# SoM.net
KiCad netlist of a schematic drawn in Altium Designer
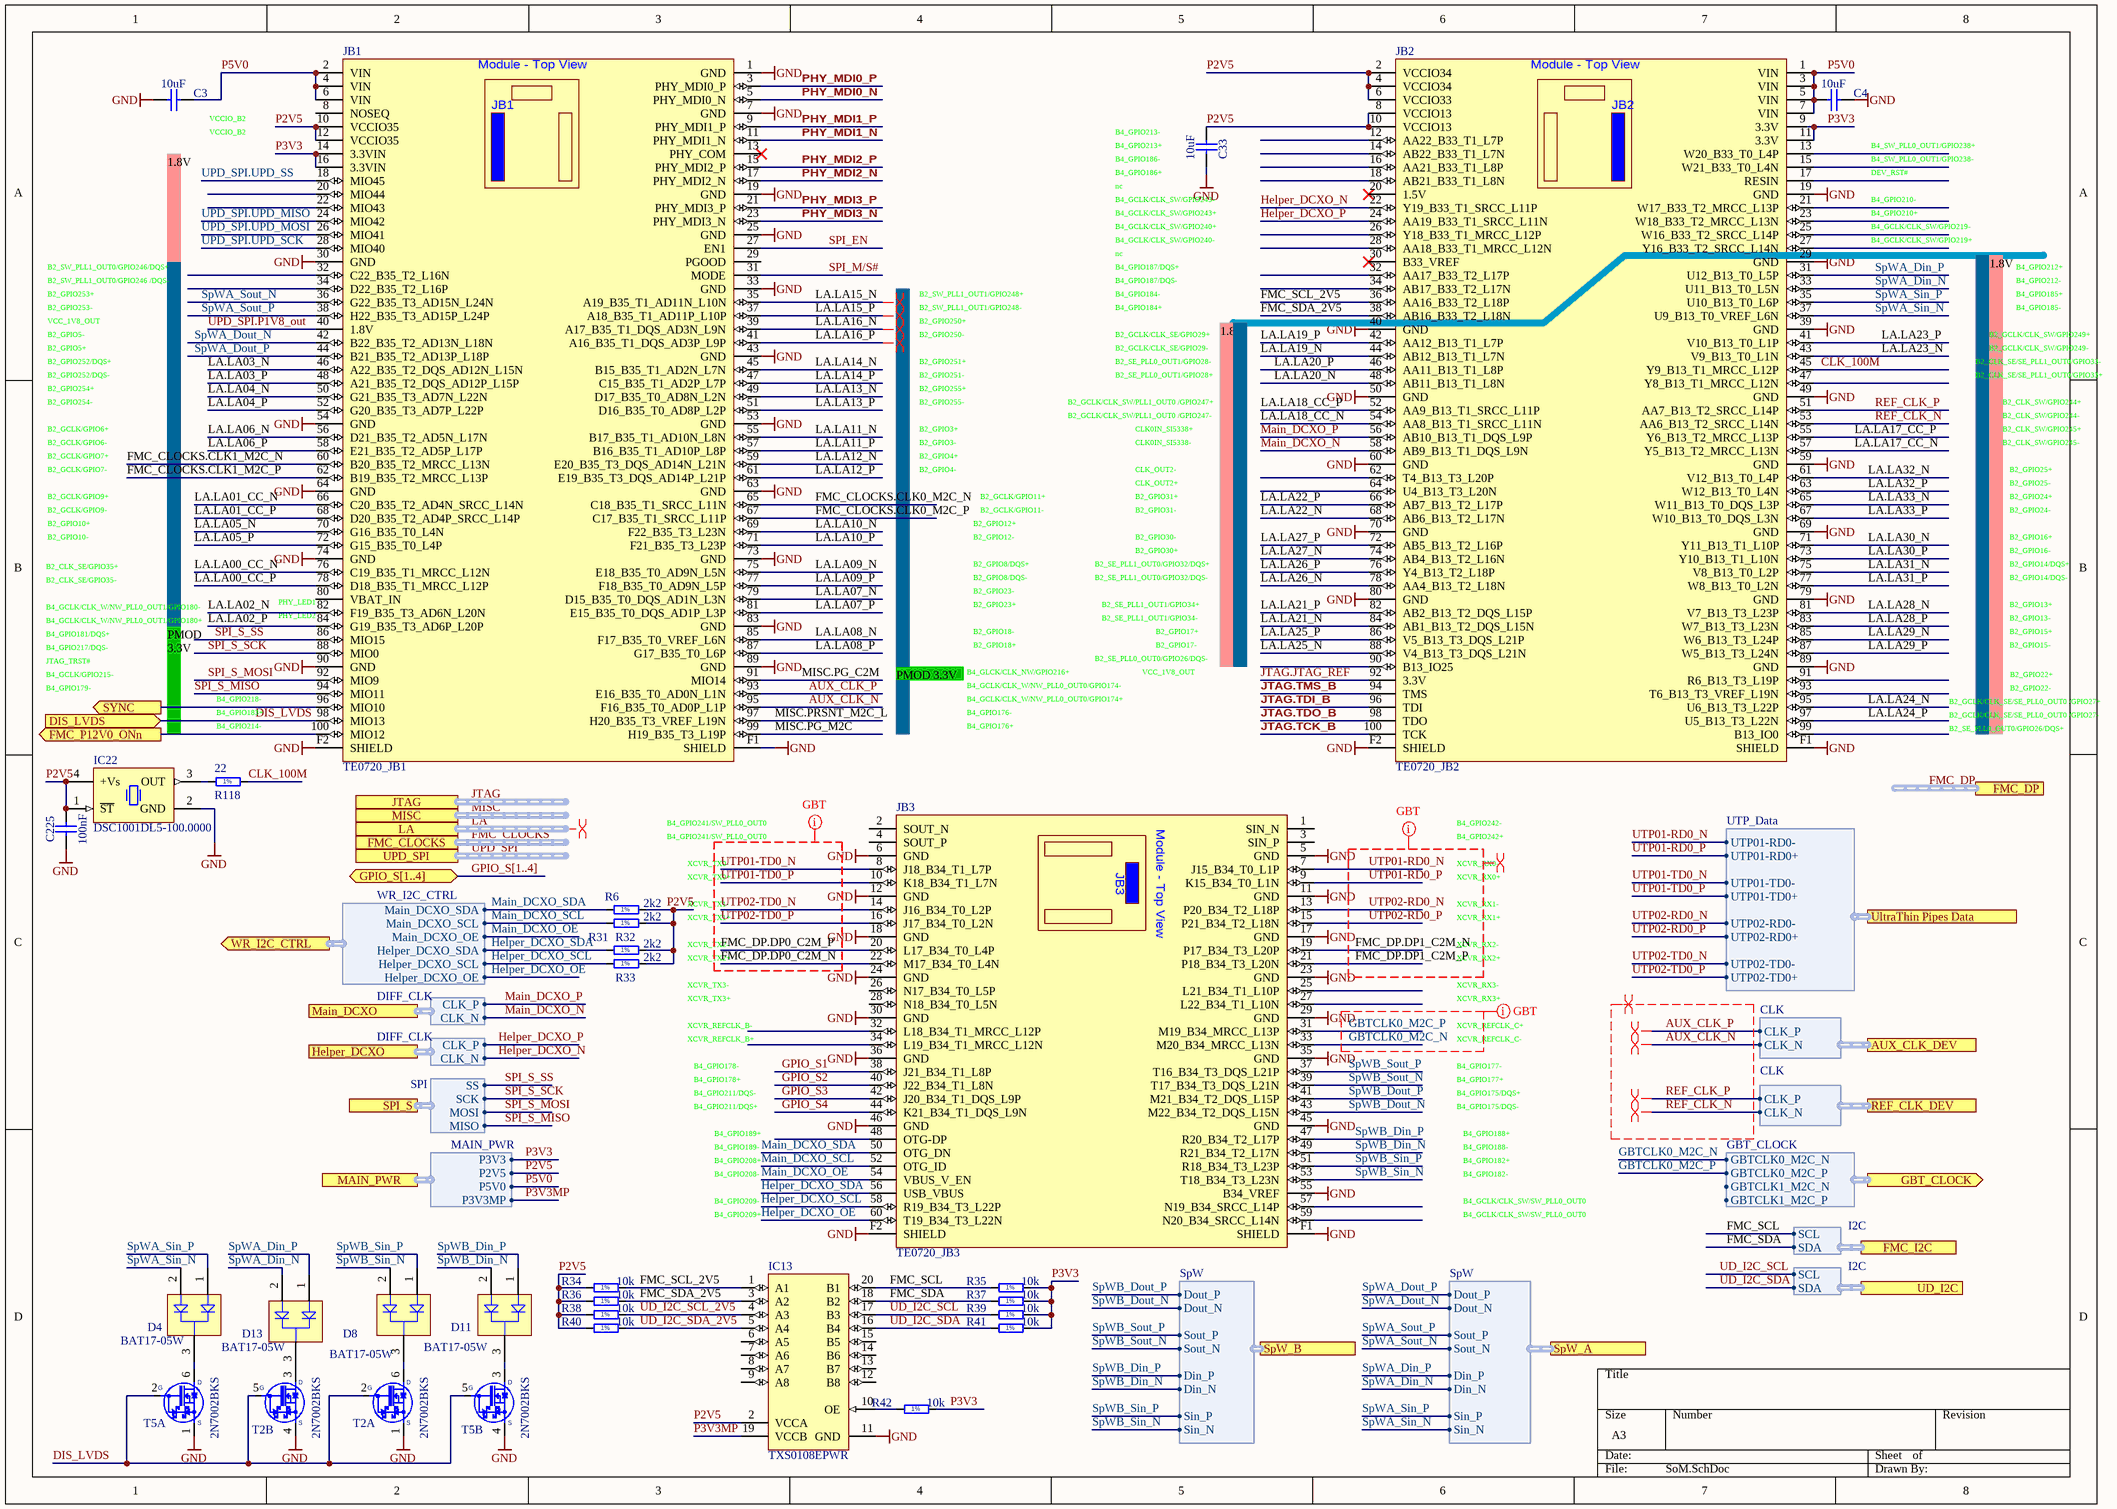
[diagram p0: SoM.SchDoc]

(export (version "E")
  (design (tool "Eeschema 10.0.6"))
  (components
    (comp (ref "C3")
      (value "10uF")
      (footprint "CAPC2012X95N")
      (description "Non-polarised capacitor")
      (fields (field (name "PART NUMBER") "CC0805_10UF_25V_10%_X5R") (field (name "VOLTAGE") "25V"))
      (libsource (lib "Capacitors") (part "Capacitor - non polarized"))
    )
    (comp (ref "C4")
      (value "10uF")
      (footprint "CAPC2012X95N")
      (description "Non-polarised capacitor")
      (fields (field (name "PART NUMBER") "CC0805_10UF_25V_10%_X5R") (field (name "VOLTAGE") "25V"))
      (libsource (lib "Capacitors") (part "Capacitor - non polarized"))
    )
    (comp (ref "C33")
      (value "10uF")
      (footprint "CAPC2012X95N")
      (description "Non-polarised capacitor")
      (fields (field (name "PART NUMBER") "CC0805_10UF_25V_10%_X5R") (field (name "VOLTAGE") "25V"))
      (libsource (lib "Capacitors") (part "Capacitor - non polarized"))
    )
    (comp (ref "C225")
      (value "100nF")
      (footprint "CAPC0603X33N")
      (description "Non-polarised capacitor")
      (fields
        (field (name "PART NUMBER") "CC0201_100NF_6.3V_10%_X5R")
        (field (name "MANUFACTURER") "GENERIC")
      )
      (libsource (lib "Capacitors") (part "Capacitor - non polarized"))
    )
    (comp (ref "D4")
      (value "BAT17-05W")
      (footprint "INF-SOT323_N")
      (description "Dual Silicon Schottky Diode, 130 mA IF Max, SOT323, Green")
      (fields (field (name "MANUFACTURER") "Infineon"))
      (libsource (lib "Altium Content Vault") (part "INF-D_A1A2K3-3"))
    )
    (comp (ref "D8")
      (value "BAT17-05W")
      (footprint "INF-SOT323_N")
      (description "Dual Silicon Schottky Diode, 130 mA IF Max, SOT323, Green")
      (fields (field (name "MANUFACTURER") "Infineon"))
      (libsource (lib "Altium Content Vault") (part "INF-D_A1A2K3-3"))
    )
    (comp (ref "D11")
      (value "BAT17-05W")
      (footprint "INF-SOT323_N")
      (description "Dual Silicon Schottky Diode, 130 mA IF Max, SOT323, Green")
      (fields (field (name "MANUFACTURER") "Infineon"))
      (libsource (lib "Altium Content Vault") (part "INF-D_A1A2K3-3"))
    )
    (comp (ref "D13")
      (value "BAT17-05W")
      (footprint "INF-SOT323_N")
      (description "Dual Silicon Schottky Diode, 130 mA IF Max, SOT323, Green")
      (fields (field (name "MANUFACTURER") "Infineon"))
      (libsource (lib "Altium Content Vault") (part "INF-D_A1A2K3-3"))
    )
    (comp (ref "IC13")
      (value "TXS0108EPWR")
      (footprint "PW0020A_M")
      (fields (field (name "MANUFACTURER") "Texas Instruments"))
      (libsource (lib "Altium Content Vault") (part "TI-TXS0108EPWR-SOP-20"))
    )
    (comp (ref "IC22")
      (value "DSC1001DL5-100.0000")
      (footprint "OSC_MICREL_2520")
      (description "MEMS 100MHz oscillator")
      (fields (field (name "MANUFACTURER") "Micrel"))
      (libsource (lib "LIBRARY_SCH") (part "OSC_DSC1001DL5-100.0000"))
    )
    (comp (ref "JB1")
      (value "TE0720_JB1")
      (footprint "LSHM-150-XXX-X-DV-A-X")
      (description "TE0720-JB1")
      (libsource (lib "TE") (part "TE0720_JB1"))
    )
    (comp (ref "JB2")
      (value "TE0720_JB2")
      (footprint "LSHM-150-XXX-X-DV-A-X")
      (description "TE0720-JB2")
      (libsource (lib "TE") (part "TE0720_JB2"))
    )
    (comp (ref "JB3")
      (value "TE0720_JB3")
      (footprint "LSHM-130-04.0-x-DV-A-S-K-TR")
      (description "TE0720-JB3")
      (libsource (lib "TE") (part "TE0720_JB3"))
    )
    (comp (ref "R6")
      (value "2k2")
      (footprint "RESC1005X40N")
      (description "Resistor - 1%")
      (fields (field (name "PART NUMBER") "R0402_2K2_1%_0.0625W_100PPM") (field (name "POWER") "0.0625W"))
      (libsource (lib "Resistors") (part "Resistor - 1%"))
    )
    (comp (ref "R31")
      (value "2k2")
      (footprint "RESC1005X40N")
      (description "Resistor - 1%")
      (fields (field (name "PART NUMBER") "R0402_2K2_1%_0.0625W_100PPM") (field (name "POWER") "0.0625W"))
      (libsource (lib "Resistors") (part "Resistor - 1%"))
    )
    (comp (ref "R32")
      (value "2k2")
      (footprint "RESC1005X40N")
      (description "Resistor - 1%")
      (fields (field (name "PART NUMBER") "R0402_2K2_1%_0.0625W_100PPM") (field (name "POWER") "0.0625W"))
      (libsource (lib "Resistors") (part "Resistor - 1%"))
    )
    (comp (ref "R33")
      (value "2k2")
      (footprint "RESC1005X40N")
      (description "Resistor - 1%")
      (fields (field (name "PART NUMBER") "R0402_2K2_1%_0.0625W_100PPM") (field (name "POWER") "0.0625W"))
      (libsource (lib "Resistors") (part "Resistor - 1%"))
    )
    (comp (ref "R34")
      (value "10k")
      (footprint "RESC1005X40N")
      (description "Resistor - 1%")
      (fields (field (name "PART NUMBER") "R0402_10K_1%_0.0625W_100PPM") (field (name "POWER") "0.0625W"))
      (libsource (lib "Resistors") (part "Resistor - 1%"))
    )
    (comp (ref "R35")
      (value "10k")
      (footprint "RESC1005X40N")
      (description "Resistor - 1%")
      (fields (field (name "PART NUMBER") "R0402_10K_1%_0.0625W_100PPM") (field (name "POWER") "0.0625W"))
      (libsource (lib "Resistors") (part "Resistor - 1%"))
    )
    (comp (ref "R36")
      (value "10k")
      (footprint "RESC1005X40N")
      (description "Resistor - 1%")
      (fields (field (name "PART NUMBER") "R0402_10K_1%_0.0625W_100PPM") (field (name "POWER") "0.0625W"))
      (libsource (lib "Resistors") (part "Resistor - 1%"))
    )
    (comp (ref "R37")
      (value "10k")
      (footprint "RESC1005X40N")
      (description "Resistor - 1%")
      (fields (field (name "PART NUMBER") "R0402_10K_1%_0.0625W_100PPM") (field (name "POWER") "0.0625W"))
      (libsource (lib "Resistors") (part "Resistor - 1%"))
    )
    (comp (ref "R38")
      (value "10k")
      (footprint "RESC1005X40N")
      (description "Resistor - 1%")
      (fields (field (name "PART NUMBER") "R0402_10K_1%_0.0625W_100PPM") (field (name "POWER") "0.0625W"))
      (libsource (lib "Resistors") (part "Resistor - 1%"))
    )
    (comp (ref "R39")
      (value "10k")
      (footprint "RESC1005X40N")
      (description "Resistor - 1%")
      (fields (field (name "PART NUMBER") "R0402_10K_1%_0.0625W_100PPM") (field (name "POWER") "0.0625W"))
      (libsource (lib "Resistors") (part "Resistor - 1%"))
    )
    (comp (ref "R40")
      (value "10k")
      (footprint "RESC1005X40N")
      (description "Resistor - 1%")
      (fields (field (name "PART NUMBER") "R0402_10K_1%_0.0625W_100PPM") (field (name "POWER") "0.0625W"))
      (libsource (lib "Resistors") (part "Resistor - 1%"))
    )
    (comp (ref "R41")
      (value "10k")
      (footprint "RESC1005X40N")
      (description "Resistor - 1%")
      (fields (field (name "PART NUMBER") "R0402_10K_1%_0.0625W_100PPM") (field (name "POWER") "0.0625W"))
      (libsource (lib "Resistors") (part "Resistor - 1%"))
    )
    (comp (ref "R42")
      (value "10k")
      (footprint "RESC1005X40N")
      (description "Resistor - 1%")
      (fields (field (name "PART NUMBER") "R0402_10K_1%_0.0625W_100PPM") (field (name "POWER") "0.0625W"))
      (libsource (lib "Resistors") (part "Resistor - 1%"))
    )
    (comp (ref "R118")
      (value "22")
      (footprint "RESC1005X40N")
      (description "Resistor - 1%")
      (fields (field (name "PART NUMBER") "R0402_22R_1%_0.0625W_100PPM") (field (name "POWER") "0.0625W"))
      (libsource (lib "Resistors") (part "Resistor - 1%"))
    )
    (comp (ref "T2")
      (value "2N7002BKS")
      (footprint "SOT65P210X110-6N")
      (description "60V, 300mA Dual N-Channel Trench MOSFET")
      (fields
        (field (name "MANUFACTURER") "NXP SEMICONDUCTORS")
        (field (name "MANUFACTURER PART NUMBER") "2N7002BKS6")
      )
      (libsource (lib "ICs And Semiconductors") (part "2N7002BKS"))
    )
    (comp (ref "T5")
      (value "2N7002BKS")
      (footprint "SOT65P210X110-6N")
      (description "60V, 300mA Dual N-Channel Trench MOSFET")
      (fields
        (field (name "MANUFACTURER") "NXP SEMICONDUCTORS")
        (field (name "MANUFACTURER PART NUMBER") "2N7002BKS6")
      )
      (libsource (lib "ICs And Semiconductors") (part "2N7002BKS"))
    )
  )
  (nets
    (net (code "16") (name "/AUX_CLK_N") (class "Default")
      (node (ref "JB1") (pin "95") (pinfunction "F16_B35_T0_AD0P_L1P_95") (pintype "bidirectional"))
    )
    (net (code "17") (name "/AUX_CLK_P") (class "Default")
      (node (ref "JB1") (pin "93") (pinfunction "E16_B35_T0_AD0N_L1N_93") (pintype "bidirectional"))
    )
    (net (code "40") (name "/CLK_100M") (class "Default")
      (node (ref "JB2") (pin "45") (pinfunction "Y9_B13_T1_MRCC_L12P_45") (pintype "bidirectional"))
      (node (ref "R118") (pin "2") (pinfunction "2_2") (pintype "passive"))
    )
    (net (code "41") (name "/DIS_LVDS") (class "Default")
      (node (ref "JB1") (pin "98") (pinfunction "MIO13_98") (pintype "bidirectional"))
      (node (ref "T2") (pin "2") (pinfunction "G_2") (pintype "passive"))
      (node (ref "T2") (pin "5") (pinfunction "G_5") (pintype "passive"))
      (node (ref "T5") (pin "2") (pinfunction "G_2") (pintype "passive"))
      (node (ref "T5") (pin "5") (pinfunction "G_5") (pintype "passive"))
    )
    (net (code "42") (name "/FMC_CLOCKS.CLK0_M2C_N") (class "Default")
      (node (ref "JB1") (pin "65") (pinfunction "C18_B35_T1_SRCC_L11N_65") (pintype "bidirectional"))
    )
    (net (code "43") (name "/FMC_CLOCKS.CLK0_M2C_P") (class "Default")
      (node (ref "JB1") (pin "67") (pinfunction "C17_B35_T1_SRCC_L11P_67") (pintype "bidirectional"))
    )
    (net (code "44") (name "/FMC_CLOCKS.CLK1_M2C_N") (class "Default")
      (node (ref "JB1") (pin "60") (pinfunction "B20_B35_T2_MRCC_L13N_60") (pintype "bidirectional"))
    )
    (net (code "45") (name "/FMC_CLOCKS.CLK1_M2C_P") (class "Default")
      (node (ref "JB1") (pin "62") (pinfunction "B19_B35_T2_MRCC_L13P_62") (pintype "bidirectional"))
    )
    (net (code "46") (name "/FMC_DP.DP0_C2M_N") (class "Default")
      (node (ref "JB3") (pin "22") (pinfunction "M17_B34_T0_L4N_22") (pintype "bidirectional"))
    )
    (net (code "47") (name "/FMC_DP.DP0_C2M_P") (class "Default")
      (node (ref "JB3") (pin "20") (pinfunction "L17_B34_T0_L4P_20") (pintype "bidirectional"))
    )
    (net (code "48") (name "/FMC_DP.DP1_C2M_N") (class "Default")
      (node (ref "JB3") (pin "19") (pinfunction "P17_B34_T3_L20P_19") (pintype "bidirectional"))
    )
    (net (code "49") (name "/FMC_DP.DP1_C2M_P") (class "Default")
      (node (ref "JB3") (pin "21") (pinfunction "P18_B34_T3_L20N_21") (pintype "bidirectional"))
    )
    (net (code "50") (name "/FMC_P12V0_ONn") (class "Default")
      (node (ref "JB1") (pin "100") (pinfunction "MIO12_100") (pintype "bidirectional"))
    )
    (net (code "51") (name "/FMC_SCL") (class "Default")
      (node (ref "IC13") (pin "20") (pinfunction "B1_20") (pintype "bidirectional"))
      (node (ref "R35") (pin "1") (pinfunction "1_1") (pintype "passive"))
    )
    (net (code "52") (name "/FMC_SCL_2V5") (class "Default")
      (node (ref "IC13") (pin "1") (pinfunction "A1_1") (pintype "bidirectional"))
      (node (ref "JB2") (pin "36") (pinfunction "AA16_B33_T2_L18P_36") (pintype "bidirectional"))
      (node (ref "R34") (pin "2") (pinfunction "2_2") (pintype "passive"))
    )
    (net (code "53") (name "/FMC_SDA") (class "Default")
      (node (ref "IC13") (pin "18") (pinfunction "B2_18") (pintype "bidirectional"))
      (node (ref "R37") (pin "1") (pinfunction "1_1") (pintype "passive"))
    )
    (net (code "54") (name "/FMC_SDA_2V5") (class "Default")
      (node (ref "IC13") (pin "3") (pinfunction "A2_3") (pintype "bidirectional"))
      (node (ref "JB2") (pin "38") (pinfunction "AB16_B33_T2_L18N_38") (pintype "bidirectional"))
      (node (ref "R36") (pin "2") (pinfunction "2_2") (pintype "passive"))
    )
    (net (code "55") (name "/GBTCLK0_M2C_N") (class "Default")
      (node (ref "JB3") (pin "33") (pinfunction "M20_B34_MRCC_L13N_33") (pintype "bidirectional"))
    )
    (net (code "56") (name "/GBTCLK0_M2C_P") (class "Default")
      (node (ref "JB3") (pin "31") (pinfunction "M19_B34_MRCC_L13P_31") (pintype "bidirectional"))
    )
    (net (code "57") (name "/GPIO_S1") (class "Default")
      (node (ref "JB3") (pin "38") (pinfunction "J21_B34_T1_L8P_38") (pintype "bidirectional"))
    )
    (net (code "58") (name "/GPIO_S2") (class "Default")
      (node (ref "JB3") (pin "40") (pinfunction "J22_B34_T1_L8N_40") (pintype "bidirectional"))
    )
    (net (code "59") (name "/GPIO_S3") (class "Default")
      (node (ref "JB3") (pin "42") (pinfunction "J20_B34_T1_DQS_L9P_42") (pintype "bidirectional"))
    )
    (net (code "60") (name "/GPIO_S4") (class "Default")
      (node (ref "JB3") (pin "44") (pinfunction "K21_B34_T1_DQS_L9N_44") (pintype "bidirectional"))
    )
    (net (code "62") (name "/Helper_DCXO_N") (class "Default")
      (node (ref "JB2") (pin "22") (pinfunction "Y19_B33_T1_SRCC_L11P_22") (pintype "bidirectional"))
    )
    (net (code "63") (name "/Helper_DCXO_OE") (class "Default")
      (node (ref "JB3") (pin "60") (pinfunction "T19_B34_T3_L22N_60") (pintype "bidirectional"))
    )
    (net (code "64") (name "/Helper_DCXO_P") (class "Default")
      (node (ref "JB2") (pin "24") (pinfunction "AA19_B33_T1_SRCC_L11N_24") (pintype "bidirectional"))
    )
    (net (code "65") (name "/Helper_DCXO_SCL") (class "Default")
      (node (ref "JB3") (pin "58") (pinfunction "R19_B34_T3_L22P_58") (pintype "bidirectional"))
      (node (ref "R33") (pin "1") (pinfunction "1_1") (pintype "passive"))
    )
    (net (code "66") (name "/Helper_DCXO_SDA") (class "Default")
      (node (ref "JB3") (pin "56") (pinfunction "USB_VBUS_56") (pintype "power_in"))
      (node (ref "R31") (pin "1") (pinfunction "1_1") (pintype "passive"))
    )
    (net (code "67") (name "/JTAG.JTAG_REF") (class "Default")
      (node (ref "JB2") (pin "92") (pinfunction "3.3V_92") (pintype "power_in"))
    )
    (net (code "68") (name "/JTAG.TCK_B") (class "Default")
      (node (ref "JB2") (pin "100") (pinfunction "TCK_100") (pintype "passive"))
    )
    (net (code "69") (name "/JTAG.TDI_B") (class "Default")
      (node (ref "JB2") (pin "96") (pinfunction "TDI_96") (pintype "passive"))
    )
    (net (code "70") (name "/JTAG.TDO_B") (class "Default")
      (node (ref "JB2") (pin "98") (pinfunction "TDO_98") (pintype "passive"))
    )
    (net (code "71") (name "/JTAG.TMS_B") (class "Default")
      (node (ref "JB2") (pin "94") (pinfunction "TMS_94") (pintype "passive"))
    )
    (net (code "72") (name "/LA.LA00_CC_N") (class "Default")
      (node (ref "JB1") (pin "76") (pinfunction "C19_B35_T1_MRCC_L12N_76") (pintype "bidirectional"))
    )
    (net (code "73") (name "/LA.LA00_CC_P") (class "Default")
      (node (ref "JB1") (pin "78") (pinfunction "D18_B35_T1_MRCC_L12P_78") (pintype "bidirectional"))
    )
    (net (code "74") (name "/LA.LA01_CC_N") (class "Default")
      (node (ref "JB1") (pin "66") (pinfunction "C20_B35_T2_AD4N_SRCC_L14N_66") (pintype "bidirectional"))
    )
    (net (code "75") (name "/LA.LA01_CC_P") (class "Default")
      (node (ref "JB1") (pin "68") (pinfunction "D20_B35_T2_AD4P_SRCC_L14P_68") (pintype "bidirectional"))
    )
    (net (code "76") (name "/LA.LA02_N") (class "Default")
      (node (ref "JB1") (pin "82") (pinfunction "F19_B35_T3_AD6N_L20N_82") (pintype "bidirectional"))
    )
    (net (code "77") (name "/LA.LA02_P") (class "Default")
      (node (ref "JB1") (pin "84") (pinfunction "G19_B35_T3_AD6P_L20P_84") (pintype "bidirectional"))
    )
    (net (code "78") (name "/LA.LA03_N") (class "Default")
      (node (ref "JB1") (pin "46") (pinfunction "A22_B35_T2_DQS_AD12N_L15N_46") (pintype "bidirectional"))
    )
    (net (code "79") (name "/LA.LA03_P") (class "Default")
      (node (ref "JB1") (pin "48") (pinfunction "A21_B35_T2_DQS_AD12P_L15P_48") (pintype "bidirectional"))
    )
    (net (code "80") (name "/LA.LA04_N") (class "Default")
      (node (ref "JB1") (pin "50") (pinfunction "G21_B35_T3_AD7N_L22N_50") (pintype "bidirectional"))
    )
    (net (code "81") (name "/LA.LA04_P") (class "Default")
      (node (ref "JB1") (pin "52") (pinfunction "G20_B35_T3_AD7P_L22P_52") (pintype "bidirectional"))
    )
    (net (code "82") (name "/LA.LA05_N") (class "Default")
      (node (ref "JB1") (pin "70") (pinfunction "G16_B35_T0_L4N_70") (pintype "bidirectional"))
    )
    (net (code "83") (name "/LA.LA05_P") (class "Default")
      (node (ref "JB1") (pin "72") (pinfunction "G15_B35_T0_L4P_72") (pintype "bidirectional"))
    )
    (net (code "84") (name "/LA.LA06_N") (class "Default")
      (node (ref "JB1") (pin "56") (pinfunction "D21_B35_T2_AD5N_L17N_56") (pintype "bidirectional"))
    )
    (net (code "85") (name "/LA.LA06_P") (class "Default")
      (node (ref "JB1") (pin "58") (pinfunction "E21_B35_T2_AD5P_L17P_58") (pintype "bidirectional"))
    )
    (net (code "86") (name "/LA.LA07_N") (class "Default")
      (node (ref "JB1") (pin "79") (pinfunction "D15_B35_T0_DQS_AD1N_L3N_79") (pintype "bidirectional"))
    )
    (net (code "87") (name "/LA.LA07_P") (class "Default")
      (node (ref "JB1") (pin "81") (pinfunction "E15_B35_T0_DQS_AD1P_L3P_81") (pintype "bidirectional"))
    )
    (net (code "88") (name "/LA.LA08_N") (class "Default")
      (node (ref "JB1") (pin "85") (pinfunction "F17_B35_T0_VREF_L6N_85") (pintype "bidirectional"))
    )
    (net (code "89") (name "/LA.LA08_P") (class "Default")
      (node (ref "JB1") (pin "87") (pinfunction "G17_B35_T0_L6P_87") (pintype "bidirectional"))
    )
    (net (code "90") (name "/LA.LA09_N") (class "Default")
      (node (ref "JB1") (pin "75") (pinfunction "E18_B35_T0_AD9N_L5N_75") (pintype "bidirectional"))
    )
    (net (code "91") (name "/LA.LA09_P") (class "Default")
      (node (ref "JB1") (pin "77") (pinfunction "F18_B35_T0_AD9N_L5P_77") (pintype "bidirectional"))
    )
    (net (code "92") (name "/LA.LA10_N") (class "Default")
      (node (ref "JB1") (pin "69") (pinfunction "F22_B35_T3_L23N_69") (pintype "bidirectional"))
    )
    (net (code "93") (name "/LA.LA10_P") (class "Default")
      (node (ref "JB1") (pin "71") (pinfunction "F21_B35_T3_L23P_71") (pintype "bidirectional"))
    )
    (net (code "94") (name "/LA.LA11_N") (class "Default")
      (node (ref "JB1") (pin "55") (pinfunction "B17_B35_T1_AD10N_L8N_55") (pintype "bidirectional"))
    )
    (net (code "95") (name "/LA.LA11_P") (class "Default")
      (node (ref "JB1") (pin "57") (pinfunction "B16_B35_T1_AD10P_L8P_57") (pintype "bidirectional"))
    )
    (net (code "96") (name "/LA.LA12_N") (class "Default")
      (node (ref "JB1") (pin "59") (pinfunction "E20_B35_T3_DQS_AD14N_L21N_59") (pintype "bidirectional"))
    )
    (net (code "97") (name "/LA.LA12_P") (class "Default")
      (node (ref "JB1") (pin "61") (pinfunction "E19_B35_T3_DQS_AD14P_L21P_61") (pintype "bidirectional"))
    )
    (net (code "98") (name "/LA.LA13_N") (class "Default")
      (node (ref "JB1") (pin "49") (pinfunction "D17_B35_T0_AD8N_L2N_49") (pintype "bidirectional"))
    )
    (net (code "99") (name "/LA.LA13_P") (class "Default")
      (node (ref "JB1") (pin "51") (pinfunction "D16_B35_T0_AD8P_L2P_51") (pintype "bidirectional"))
    )
    (net (code "100") (name "/LA.LA14_N") (class "Default")
      (node (ref "JB1") (pin "45") (pinfunction "B15_B35_T1_AD2N_L7N_45") (pintype "bidirectional"))
    )
    (net (code "101") (name "/LA.LA14_P") (class "Default")
      (node (ref "JB1") (pin "47") (pinfunction "C15_B35_T1_AD2P_L7P_47") (pintype "bidirectional"))
    )
    (net (code "102") (name "/LA.LA15_N") (class "Default")
      (node (ref "JB1") (pin "35") (pinfunction "A19_B35_T1_AD11N_L10N_35") (pintype "bidirectional"))
    )
    (net (code "103") (name "/LA.LA15_P") (class "Default")
      (node (ref "JB1") (pin "37") (pinfunction "A18_B35_T1_AD11P_L10P_37") (pintype "bidirectional"))
    )
    (net (code "104") (name "/LA.LA16_N") (class "Default")
      (node (ref "JB1") (pin "39") (pinfunction "A17_B35_T1_DQS_AD3N_L9N_39") (pintype "bidirectional"))
    )
    (net (code "105") (name "/LA.LA16_P") (class "Default")
      (node (ref "JB1") (pin "41") (pinfunction "A16_B35_T1_DQS_AD3P_L9P_41") (pintype "bidirectional"))
    )
    (net (code "106") (name "/LA.LA17_CC_N") (class "Default")
      (node (ref "JB2") (pin "57") (pinfunction "Y5_B13_T2_MRCC_L13N_57") (pintype "bidirectional"))
    )
    (net (code "107") (name "/LA.LA17_CC_P") (class "Default")
      (node (ref "JB2") (pin "55") (pinfunction "Y6_B13_T2_MRCC_L13P_55") (pintype "bidirectional"))
    )
    (net (code "108") (name "/LA.LA18_CC_N") (class "Default")
      (node (ref "JB2") (pin "54") (pinfunction "AA8_B13_T1_SRCC_L11N_54") (pintype "bidirectional"))
    )
    (net (code "109") (name "/LA.LA18_CC_P") (class "Default")
      (node (ref "JB2") (pin "52") (pinfunction "AA9_B13_T1_SRCC_L11P_52") (pintype "bidirectional"))
    )
    (net (code "110") (name "/LA.LA19_N") (class "Default")
      (node (ref "JB2") (pin "44") (pinfunction "AB12_B13_T1_L7N_44") (pintype "bidirectional"))
    )
    (net (code "111") (name "/LA.LA19_P") (class "Default")
      (node (ref "JB2") (pin "42") (pinfunction "AA12_B13_T1_L7P_42") (pintype "bidirectional"))
    )
    (net (code "112") (name "/LA.LA20_N") (class "Default")
      (node (ref "JB2") (pin "48") (pinfunction "AB11_B13_T1_L8N_48") (pintype "bidirectional"))
    )
    (net (code "113") (name "/LA.LA20_P") (class "Default")
      (node (ref "JB2") (pin "46") (pinfunction "AA11_B13_T1_L8P_46") (pintype "bidirectional"))
    )
    (net (code "114") (name "/LA.LA21_N") (class "Default")
      (node (ref "JB2") (pin "84") (pinfunction "AB1_B13_T2_DQS_L15N_84") (pintype "bidirectional"))
    )
    (net (code "115") (name "/LA.LA21_P") (class "Default")
      (node (ref "JB2") (pin "82") (pinfunction "AB2_B13_T2_DQS_L15P_82") (pintype "bidirectional"))
    )
    (net (code "116") (name "/LA.LA22_N") (class "Default")
      (node (ref "JB2") (pin "68") (pinfunction "AB6_B13_T2_L17N_68") (pintype "bidirectional"))
    )
    (net (code "117") (name "/LA.LA22_P") (class "Default")
      (node (ref "JB2") (pin "66") (pinfunction "AB7_B13_T2_L17P_66") (pintype "bidirectional"))
    )
    (net (code "118") (name "/LA.LA23_N") (class "Default")
      (node (ref "JB2") (pin "43") (pinfunction "V9_B13_T0_L1N_43") (pintype "bidirectional"))
    )
    (net (code "119") (name "/LA.LA23_P") (class "Default")
      (node (ref "JB2") (pin "41") (pinfunction "V10_B13_T0_L1P_41") (pintype "bidirectional"))
    )
    (net (code "120") (name "/LA.LA24_N") (class "Default")
      (node (ref "JB2") (pin "95") (pinfunction "U6_B13_T3_L22P_95") (pintype "bidirectional"))
    )
    (net (code "121") (name "/LA.LA24_P") (class "Default")
      (node (ref "JB2") (pin "97") (pinfunction "U5_B13_T3_L22N_97") (pintype "bidirectional"))
    )
    (net (code "122") (name "/LA.LA25_N") (class "Default")
      (node (ref "JB2") (pin "88") (pinfunction "V4_B13_T3_DQS_L21N_88") (pintype "bidirectional"))
    )
    (net (code "123") (name "/LA.LA25_P") (class "Default")
      (node (ref "JB2") (pin "86") (pinfunction "V5_B13_T3_DQS_L21P_86") (pintype "bidirectional"))
    )
    (net (code "124") (name "/LA.LA26_N") (class "Default")
      (node (ref "JB2") (pin "78") (pinfunction "AA4_B13_T2_L18N_78") (pintype "bidirectional"))
    )
    (net (code "125") (name "/LA.LA26_P") (class "Default")
      (node (ref "JB2") (pin "76") (pinfunction "Y4_B13_T2_L18P_76") (pintype "bidirectional"))
    )
    (net (code "126") (name "/LA.LA27_N") (class "Default")
      (node (ref "JB2") (pin "74") (pinfunction "AB4_B13_T2_L16N_74") (pintype "bidirectional"))
    )
    (net (code "127") (name "/LA.LA27_P") (class "Default")
      (node (ref "JB2") (pin "72") (pinfunction "AB5_B13_T2_L16P_72") (pintype "bidirectional"))
    )
    (net (code "128") (name "/LA.LA28_N") (class "Default")
      (node (ref "JB2") (pin "81") (pinfunction "V7_B13_T3_L23P_81") (pintype "bidirectional"))
    )
    (net (code "129") (name "/LA.LA28_P") (class "Default")
      (node (ref "JB2") (pin "83") (pinfunction "W7_B13_T3_L23N_83") (pintype "bidirectional"))
    )
    (net (code "130") (name "/LA.LA29_N") (class "Default")
      (node (ref "JB2") (pin "85") (pinfunction "W6_B13_T3_L24P_85") (pintype "bidirectional"))
    )
    (net (code "131") (name "/LA.LA29_P") (class "Default")
      (node (ref "JB2") (pin "87") (pinfunction "W5_B13_T3_L24N_87") (pintype "bidirectional"))
    )
    (net (code "132") (name "/LA.LA30_N") (class "Default")
      (node (ref "JB2") (pin "71") (pinfunction "Y11_B13_T1_L10P_71") (pintype "bidirectional"))
    )
    (net (code "133") (name "/LA.LA30_P") (class "Default")
      (node (ref "JB2") (pin "73") (pinfunction "Y10_B13_T1_L10N_73") (pintype "bidirectional"))
    )
    (net (code "134") (name "/LA.LA31_N") (class "Default")
      (node (ref "JB2") (pin "75") (pinfunction "V8_B13_T0_L2P_75") (pintype "bidirectional"))
    )
    (net (code "135") (name "/LA.LA31_P") (class "Default")
      (node (ref "JB2") (pin "77") (pinfunction "W8_B13_T0_L2N_77") (pintype "bidirectional"))
    )
    (net (code "136") (name "/LA.LA32_N") (class "Default")
      (node (ref "JB2") (pin "61") (pinfunction "V12_B13_T0_L4P_61") (pintype "bidirectional"))
    )
    (net (code "137") (name "/LA.LA32_P") (class "Default")
      (node (ref "JB2") (pin "63") (pinfunction "W12_B13_T0_L4N_63") (pintype "bidirectional"))
    )
    (net (code "138") (name "/LA.LA33_N") (class "Default")
      (node (ref "JB2") (pin "65") (pinfunction "W11_B13_T0_DQS_L3P_65") (pintype "bidirectional"))
    )
    (net (code "139") (name "/LA.LA33_P") (class "Default")
      (node (ref "JB2") (pin "67") (pinfunction "W10_B13_T0_DQS_L3N_67") (pintype "bidirectional"))
    )
    (net (code "140") (name "/MISC.PG_C2M") (class "Default")
      (node (ref "JB1") (pin "91") (pinfunction "MIO14_91") (pintype "bidirectional"))
    )
    (net (code "141") (name "/MISC.PG_M2C") (class "Default")
      (node (ref "JB1") (pin "99") (pinfunction "H19_B35_T3_L19P_99") (pintype "bidirectional"))
    )
    (net (code "142") (name "/MISC.PRSNT_M2C_L") (class "Default")
      (node (ref "JB1") (pin "97") (pinfunction "H20_B35_T3_VREF_L19N_97") (pintype "bidirectional"))
    )
    (net (code "143") (name "/Main_DCXO_N") (class "Default")
      (node (ref "JB2") (pin "58") (pinfunction "AB9_B13_T1_DQS_L9N_58") (pintype "bidirectional"))
    )
    (net (code "144") (name "/Main_DCXO_OE") (class "Default")
      (node (ref "JB3") (pin "54") (pinfunction "VBUS_V_EN_54") (pintype "power_in"))
    )
    (net (code "145") (name "/Main_DCXO_P") (class "Default")
      (node (ref "JB2") (pin "56") (pinfunction "AB10_B13_T1_DQS_L9P_56") (pintype "bidirectional"))
    )
    (net (code "146") (name "/Main_DCXO_SCL") (class "Default")
      (node (ref "JB3") (pin "52") (pinfunction "OTG_ID_52") (pintype "power_in"))
      (node (ref "R32") (pin "1") (pinfunction "1_1") (pintype "passive"))
    )
    (net (code "147") (name "/Main_DCXO_SDA") (class "Default")
      (node (ref "JB3") (pin "50") (pinfunction "OTG_DN_50") (pintype "power_in"))
      (node (ref "R6") (pin "1") (pinfunction "1_1") (pintype "passive"))
    )
    (net (code "148") (name "/P2V5") (class "Default")
      (node (ref "C225") (pin "2") (pinfunction "2_2") (pintype "passive"))
      (node (ref "C33") (pin "1") (pinfunction "1_1") (pintype "passive"))
      (node (ref "IC13") (pin "2") (pinfunction "VCCA_2") (pintype "power_in"))
      (node (ref "IC22") (pin "1") (pinfunction "ST_1") (pintype "input"))
      (node (ref "IC22") (pin "4") (pinfunction "+Vs_4") (pintype "power_in"))
      (node (ref "JB1") (pin "10") (pinfunction "VCCIO35_10") (pintype "power_in"))
      (node (ref "JB1") (pin "12") (pinfunction "VCCIO35_12") (pintype "power_in"))
      (node (ref "JB2") (pin "10") (pinfunction "VCCIO13_10") (pintype "power_in"))
      (node (ref "JB2") (pin "2") (pinfunction "VCCIO34_2") (pintype "power_in"))
      (node (ref "JB2") (pin "4") (pinfunction "VCCIO34_4") (pintype "power_in"))
      (node (ref "JB2") (pin "6") (pinfunction "VCCIO33_6") (pintype "power_in"))
      (node (ref "JB2") (pin "8") (pinfunction "VCCIO13_8") (pintype "power_in"))
      (node (ref "R31") (pin "2") (pinfunction "2_2") (pintype "passive"))
      (node (ref "R32") (pin "2") (pinfunction "2_2") (pintype "passive"))
      (node (ref "R33") (pin "2") (pinfunction "2_2") (pintype "passive"))
      (node (ref "R34") (pin "1") (pinfunction "1_1") (pintype "passive"))
      (node (ref "R36") (pin "1") (pinfunction "1_1") (pintype "passive"))
      (node (ref "R38") (pin "1") (pinfunction "1_1") (pintype "passive"))
      (node (ref "R40") (pin "1") (pinfunction "1_1") (pintype "passive"))
      (node (ref "R6") (pin "2") (pinfunction "2_2") (pintype "passive"))
    )
    (net (code "149") (name "/P3V3") (class "Default")
      (node (ref "JB1") (pin "14") (pinfunction "3.3VIN_14") (pintype "power_in"))
      (node (ref "JB1") (pin "16") (pinfunction "3.3VIN_16") (pintype "power_in"))
      (node (ref "JB2") (pin "11") (pinfunction "3.3V_11") (pintype "power_in"))
      (node (ref "JB2") (pin "9") (pinfunction "3.3V_9") (pintype "power_in"))
      (node (ref "R35") (pin "2") (pinfunction "2_2") (pintype "passive"))
      (node (ref "R37") (pin "2") (pinfunction "2_2") (pintype "passive"))
      (node (ref "R39") (pin "2") (pinfunction "2_2") (pintype "passive"))
      (node (ref "R41") (pin "2") (pinfunction "2_2") (pintype "passive"))
      (node (ref "R42") (pin "2") (pinfunction "2_2") (pintype "passive"))
    )
    (net (code "150") (name "/P3V3MP") (class "Default")
      (node (ref "IC13") (pin "19") (pinfunction "VCCB_19") (pintype "power_in"))
    )
    (net (code "151") (name "/P5V0") (class "Default")
      (node (ref "C3") (pin "1") (pinfunction "1_1") (pintype "passive"))
      (node (ref "C4") (pin "2") (pinfunction "2_2") (pintype "passive"))
      (node (ref "JB1") (pin "2") (pinfunction "VIN_2") (pintype "power_in"))
      (node (ref "JB1") (pin "4") (pinfunction "VIN_4") (pintype "power_in"))
      (node (ref "JB1") (pin "6") (pinfunction "VIN_6") (pintype "power_in"))
      (node (ref "JB2") (pin "1") (pinfunction "VIN_1") (pintype "power_in"))
      (node (ref "JB2") (pin "3") (pinfunction "VIN_3") (pintype "power_in"))
      (node (ref "JB2") (pin "5") (pinfunction "VIN_5") (pintype "power_in"))
      (node (ref "JB2") (pin "7") (pinfunction "VIN_7") (pintype "power_in"))
    )
    (net (code "152") (name "/PHY_MDI0_N") (class "Default")
      (node (ref "JB1") (pin "5") (pinfunction "PHY_MDI0_N_5") (pintype "bidirectional"))
    )
    (net (code "153") (name "/PHY_MDI0_P") (class "Default")
      (node (ref "JB1") (pin "3") (pinfunction "PHY_MDI0_P_3") (pintype "bidirectional"))
    )
    (net (code "154") (name "/PHY_MDI1_N") (class "Default")
      (node (ref "JB1") (pin "11") (pinfunction "PHY_MDI1_N_11") (pintype "bidirectional"))
    )
    (net (code "155") (name "/PHY_MDI1_P") (class "Default")
      (node (ref "JB1") (pin "9") (pinfunction "PHY_MDI1_P_9") (pintype "bidirectional"))
    )
    (net (code "156") (name "/PHY_MDI2_N") (class "Default")
      (node (ref "JB1") (pin "17") (pinfunction "PHY_MDI2_N_17") (pintype "bidirectional"))
    )
    (net (code "157") (name "/PHY_MDI2_P") (class "Default")
      (node (ref "JB1") (pin "15") (pinfunction "PHY_MDI2_P_15") (pintype "bidirectional"))
    )
    (net (code "158") (name "/PHY_MDI3_N") (class "Default")
      (node (ref "JB1") (pin "23") (pinfunction "PHY_MDI3_N_23") (pintype "bidirectional"))
    )
    (net (code "159") (name "/PHY_MDI3_P") (class "Default")
      (node (ref "JB1") (pin "21") (pinfunction "PHY_MDI3_P_21") (pintype "bidirectional"))
    )
    (net (code "160") (name "/REF_CLK_N") (class "Default")
      (node (ref "JB2") (pin "53") (pinfunction "AA6_B13_T2_SRCC_L14N_53") (pintype "bidirectional"))
    )
    (net (code "161") (name "/REF_CLK_P") (class "Default")
      (node (ref "JB2") (pin "51") (pinfunction "AA7_B13_T2_SRCC_L14P_51") (pintype "bidirectional"))
    )
    (net (code "162") (name "/SPI_EN") (class "Default")
      (node (ref "JB1") (pin "27") (pinfunction "EN1_27") (pintype "passive"))
    )
    (net (code "163") (name "/SPI_M{slash}S#") (class "Default")
      (node (ref "JB1") (pin "31") (pinfunction "MODE_31") (pintype "passive"))
    )
    (net (code "164") (name "/SPI_S_MISO") (class "Default")
      (node (ref "JB1") (pin "94") (pinfunction "MIO11_94") (pintype "bidirectional"))
    )
    (net (code "165") (name "/SPI_S_MOSI") (class "Default")
      (node (ref "JB1") (pin "92") (pinfunction "MIO9_92") (pintype "bidirectional"))
    )
    (net (code "166") (name "/SPI_S_SCK") (class "Default")
      (node (ref "JB1") (pin "88") (pinfunction "MIO0_88") (pintype "bidirectional"))
    )
    (net (code "167") (name "/SPI_S_SS") (class "Default")
      (node (ref "JB1") (pin "86") (pinfunction "MIO15_86") (pintype "bidirectional"))
    )
    (net (code "168") (name "/SYNC") (class "Default")
      (node (ref "JB1") (pin "96") (pinfunction "MIO10_96") (pintype "bidirectional"))
    )
    (net (code "169") (name "/SpWA_Din_N") (class "Default")
      (node (ref "D13") (pin "2") (pinfunction "A2_2") (pintype "passive"))
      (node (ref "JB2") (pin "33") (pinfunction "U11_B13_T0_L5N_33") (pintype "bidirectional"))
    )
    (net (code "170") (name "/SpWA_Din_P") (class "Default")
      (node (ref "D13") (pin "1") (pinfunction "A1_1") (pintype "passive"))
      (node (ref "JB2") (pin "31") (pinfunction "U12_B13_T0_L5P_31") (pintype "bidirectional"))
    )
    (net (code "171") (name "/SpWA_Dout_N") (class "Default")
      (node (ref "JB1") (pin "42") (pinfunction "B22_B35_T2_AD13N_L18N_42") (pintype "bidirectional"))
    )
    (net (code "172") (name "/SpWA_Dout_P") (class "Default")
      (node (ref "JB1") (pin "44") (pinfunction "B21_B35_T2_AD13P_L18P_44") (pintype "bidirectional"))
    )
    (net (code "173") (name "/SpWA_Sin_N") (class "Default")
      (node (ref "D4") (pin "2") (pinfunction "A2_2") (pintype "passive"))
      (node (ref "JB2") (pin "37") (pinfunction "U9_B13_T0_VREF_L6N_37") (pintype "bidirectional"))
    )
    (net (code "174") (name "/SpWA_Sin_P") (class "Default")
      (node (ref "D4") (pin "1") (pinfunction "A1_1") (pintype "passive"))
      (node (ref "JB2") (pin "35") (pinfunction "U10_B13_T0_L6P_35") (pintype "bidirectional"))
    )
    (net (code "175") (name "/SpWA_Sout_N") (class "Default")
      (node (ref "JB1") (pin "36") (pinfunction "G22_B35_T3_AD15N_L24N_36") (pintype "bidirectional"))
    )
    (net (code "176") (name "/SpWA_Sout_P") (class "Default")
      (node (ref "JB1") (pin "38") (pinfunction "H22_B35_T3_AD15P_L24P_38") (pintype "bidirectional"))
    )
    (net (code "177") (name "/SpWB_Din_N") (class "Default")
      (node (ref "D11") (pin "2") (pinfunction "A2_2") (pintype "passive"))
      (node (ref "JB3") (pin "49") (pinfunction "R21_B34_T2_L17N_49") (pintype "bidirectional"))
    )
    (net (code "178") (name "/SpWB_Din_P") (class "Default")
      (node (ref "D11") (pin "1") (pinfunction "A1_1") (pintype "passive"))
      (node (ref "JB3") (pin "47") (pinfunction "R20_B34_T2_L17P_47") (pintype "bidirectional"))
    )
    (net (code "179") (name "/SpWB_Dout_N") (class "Default")
      (node (ref "JB3") (pin "43") (pinfunction "M22_B34_T2_DQS_L15N_43") (pintype "bidirectional"))
    )
    (net (code "180") (name "/SpWB_Dout_P") (class "Default")
      (node (ref "JB3") (pin "41") (pinfunction "M21_B34_T2_DQS_L15P_41") (pintype "bidirectional"))
    )
    (net (code "181") (name "/SpWB_Sin_N") (class "Default")
      (node (ref "D8") (pin "2") (pinfunction "A2_2") (pintype "passive"))
      (node (ref "JB3") (pin "53") (pinfunction "T18_B34_T3_L23N_53") (pintype "bidirectional"))
    )
    (net (code "182") (name "/SpWB_Sin_P") (class "Default")
      (node (ref "D8") (pin "1") (pinfunction "A1_1") (pintype "passive"))
      (node (ref "JB3") (pin "51") (pinfunction "R18_B34_T3_L23P_51") (pintype "bidirectional"))
    )
    (net (code "183") (name "/SpWB_Sout_N") (class "Default")
      (node (ref "JB3") (pin "39") (pinfunction "T17_B34_T3_DQS_L21N_39") (pintype "bidirectional"))
    )
    (net (code "184") (name "/SpWB_Sout_P") (class "Default")
      (node (ref "JB3") (pin "37") (pinfunction "T16_B34_T3_DQS_L21P_37") (pintype "bidirectional"))
    )
    (net (code "185") (name "/UD_I2C_SCL") (class "Default")
      (node (ref "IC13") (pin "17") (pinfunction "B3_17") (pintype "bidirectional"))
      (node (ref "R39") (pin "1") (pinfunction "1_1") (pintype "passive"))
    )
    (net (code "186") (name "/UD_I2C_SCL_2V5") (class "Default")
      (node (ref "IC13") (pin "4") (pinfunction "A3_4") (pintype "bidirectional"))
      (node (ref "R38") (pin "2") (pinfunction "2_2") (pintype "passive"))
    )
    (net (code "187") (name "/UD_I2C_SDA") (class "Default")
      (node (ref "IC13") (pin "16") (pinfunction "B4_16") (pintype "bidirectional"))
      (node (ref "R41") (pin "1") (pinfunction "1_1") (pintype "passive"))
    )
    (net (code "188") (name "/UD_I2C_SDA_2V5") (class "Default")
      (node (ref "IC13") (pin "5") (pinfunction "A4_5") (pintype "bidirectional"))
      (node (ref "R40") (pin "2") (pinfunction "2_2") (pintype "passive"))
    )
    (net (code "189") (name "/UPD_SPI.P1V8_out") (class "Default")
      (node (ref "JB1") (pin "40") (pinfunction "1.8V_40") (pintype "power_in"))
    )
    (net (code "190") (name "/UPD_SPI.UPD_MISO") (class "Default")
      (node (ref "JB1") (pin "24") (pinfunction "MIO42_24") (pintype "bidirectional"))
    )
    (net (code "191") (name "/UPD_SPI.UPD_MOSI") (class "Default")
      (node (ref "JB1") (pin "26") (pinfunction "MIO41_26") (pintype "bidirectional"))
    )
    (net (code "192") (name "/UPD_SPI.UPD_SCK") (class "Default")
      (node (ref "JB1") (pin "28") (pinfunction "MIO40_28") (pintype "bidirectional"))
    )
    (net (code "193") (name "/UPD_SPI.UPD_SS") (class "Default")
      (node (ref "JB1") (pin "18") (pinfunction "MIO45_18") (pintype "bidirectional"))
    )
    (net (code "194") (name "/UTP01-RD0_N") (class "Default")
      (node (ref "JB3") (pin "7") (pinfunction "J15_B34_T0_L1P_7") (pintype "bidirectional"))
    )
    (net (code "195") (name "/UTP01-RD0_P") (class "Default")
      (node (ref "JB3") (pin "9") (pinfunction "K15_B34_T0_L1N_9") (pintype "bidirectional"))
    )
    (net (code "196") (name "/UTP01-TD0_N") (class "Default")
      (node (ref "JB3") (pin "8") (pinfunction "J18_B34_T1_L7P_8") (pintype "bidirectional"))
    )
    (net (code "197") (name "/UTP01-TD0_P") (class "Default")
      (node (ref "JB3") (pin "10") (pinfunction "K18_B34_T1_L7N_10") (pintype "bidirectional"))
    )
    (net (code "198") (name "/UTP02-RD0_N") (class "Default")
      (node (ref "JB3") (pin "13") (pinfunction "P20_B34_T2_L18P_13") (pintype "bidirectional"))
    )
    (net (code "199") (name "/UTP02-RD0_P") (class "Default")
      (node (ref "JB3") (pin "15") (pinfunction "P21_B34_T2_L18N_15") (pintype "bidirectional"))
    )
    (net (code "200") (name "/UTP02-TD0_N") (class "Default")
      (node (ref "JB3") (pin "14") (pinfunction "J16_B34_T0_L2P_14") (pintype "bidirectional"))
    )
    (net (code "201") (name "/UTP02-TD0_P") (class "Default")
      (node (ref "JB3") (pin "16") (pinfunction "J17_B34_T0_L2N_16") (pintype "bidirectional"))
    )
    (net (code "236") (name "GND") (class "Default")
      (node (ref "C225") (pin "1") (pinfunction "1_1") (pintype "passive"))
      (node (ref "C3") (pin "2") (pinfunction "2_2") (pintype "passive"))
      (node (ref "C33") (pin "2") (pinfunction "2_2") (pintype "passive"))
      (node (ref "C4") (pin "1") (pinfunction "1_1") (pintype "passive"))
      (node (ref "IC13") (pin "11") (pinfunction "GND_11") (pintype "power_in"))
      (node (ref "IC22") (pin "2") (pinfunction "GND_2") (pintype "power_in"))
      (node (ref "JB1") (pin "1") (pinfunction "GND_1") (pintype "power_in"))
      (node (ref "JB1") (pin "19") (pinfunction "GND_19") (pintype "power_in"))
      (node (ref "JB1") (pin "25") (pinfunction "GND_25") (pintype "power_in"))
      (node (ref "JB1") (pin "30") (pinfunction "GND_30") (pintype "power_in"))
      (node (ref "JB1") (pin "33") (pinfunction "GND_33") (pintype "power_in"))
      (node (ref "JB1") (pin "43") (pinfunction "GND_43") (pintype "power_in"))
      (node (ref "JB1") (pin "53") (pinfunction "GND_53") (pintype "power_in"))
      (node (ref "JB1") (pin "54") (pinfunction "GND_54") (pintype "power_in"))
      (node (ref "JB1") (pin "63") (pinfunction "GND_63") (pintype "power_in"))
      (node (ref "JB1") (pin "64") (pinfunction "GND_64") (pintype "power_in"))
      (node (ref "JB1") (pin "7") (pinfunction "GND_7") (pintype "power_in"))
      (node (ref "JB1") (pin "73") (pinfunction "GND_73") (pintype "power_in"))
      (node (ref "JB1") (pin "74") (pinfunction "GND_74") (pintype "power_in"))
      (node (ref "JB1") (pin "83") (pinfunction "GND_83") (pintype "power_in"))
      (node (ref "JB1") (pin "89") (pinfunction "GND_89") (pintype "power_in"))
      (node (ref "JB1") (pin "90") (pinfunction "GND_90") (pintype "power_in"))
      (node (ref "JB1") (pin "F1") (pinfunction "SHIELD_F1") (pintype "power_in"))
      (node (ref "JB1") (pin "F2") (pinfunction "SHIELD_F2") (pintype "power_in"))
      (node (ref "JB2") (pin "19") (pinfunction "GND_19") (pintype "power_in"))
      (node (ref "JB2") (pin "29") (pinfunction "GND_29") (pintype "power_in"))
      (node (ref "JB2") (pin "39") (pinfunction "GND_39") (pintype "power_in"))
      (node (ref "JB2") (pin "40") (pinfunction "GND_40") (pintype "power_in"))
      (node (ref "JB2") (pin "49") (pinfunction "GND_49") (pintype "power_in"))
      (node (ref "JB2") (pin "50") (pinfunction "GND_50") (pintype "power_in"))
      (node (ref "JB2") (pin "59") (pinfunction "GND_59") (pintype "power_in"))
      (node (ref "JB2") (pin "60") (pinfunction "GND_60") (pintype "power_in"))
      (node (ref "JB2") (pin "69") (pinfunction "GND_69") (pintype "power_in"))
      (node (ref "JB2") (pin "70") (pinfunction "GND_70") (pintype "power_in"))
      (node (ref "JB2") (pin "79") (pinfunction "GND_79") (pintype "power_in"))
      (node (ref "JB2") (pin "80") (pinfunction "GND_80") (pintype "power_in"))
      (node (ref "JB2") (pin "89") (pinfunction "GND_89") (pintype "power_in"))
      (node (ref "JB2") (pin "F1") (pinfunction "SHIELD_F1") (pintype "power_in"))
      (node (ref "JB2") (pin "F2") (pinfunction "SHIELD_F2") (pintype "power_in"))
      (node (ref "JB3") (pin "11") (pinfunction "GND_11") (pintype "power_in"))
      (node (ref "JB3") (pin "12") (pinfunction "GND_12") (pintype "power_in"))
      (node (ref "JB3") (pin "17") (pinfunction "GND_17") (pintype "power_in"))
      (node (ref "JB3") (pin "18") (pinfunction "GND_18") (pintype "power_in"))
      (node (ref "JB3") (pin "23") (pinfunction "GND_23") (pintype "power_in"))
      (node (ref "JB3") (pin "24") (pinfunction "GND_24") (pintype "power_in"))
      (node (ref "JB3") (pin "29") (pinfunction "GND_29") (pintype "power_in"))
      (node (ref "JB3") (pin "30") (pinfunction "GND_30") (pintype "power_in"))
      (node (ref "JB3") (pin "35") (pinfunction "GND_35") (pintype "power_in"))
      (node (ref "JB3") (pin "36") (pinfunction "GND_36") (pintype "power_in"))
      (node (ref "JB3") (pin "45") (pinfunction "GND_45") (pintype "power_in"))
      (node (ref "JB3") (pin "46") (pinfunction "GND_46") (pintype "power_in"))
      (node (ref "JB3") (pin "5") (pinfunction "GND_5") (pintype "power_in"))
      (node (ref "JB3") (pin "55") (pinfunction "B34_VREF_55") (pintype "power_in"))
      (node (ref "JB3") (pin "6") (pinfunction "GND_6") (pintype "power_in"))
      (node (ref "JB3") (pin "F1") (pinfunction "SHIELD_F1") (pintype "power_in"))
      (node (ref "JB3") (pin "F2") (pinfunction "SHIELD_F2") (pintype "power_in"))
      (node (ref "T2") (pin "1") (pinfunction "S_1") (pintype "passive"))
      (node (ref "T2") (pin "4") (pinfunction "S_4") (pintype "passive"))
      (node (ref "T5") (pin "1") (pinfunction "S_1") (pintype "passive"))
      (node (ref "T5") (pin "4") (pinfunction "S_4") (pintype "passive"))
    )
    (net (code "237") (name "Net-(D4-K)") (class "Default")
      (node (ref "D4") (pin "3") (pinfunction "K_3") (pintype "passive"))
      (node (ref "T5") (pin "6") (pinfunction "D_6") (pintype "passive"))
    )
    (net (code "238") (name "Net-(D8-K)") (class "Default")
      (node (ref "D8") (pin "3") (pinfunction "K_3") (pintype "passive"))
      (node (ref "T2") (pin "6") (pinfunction "D_6") (pintype "passive"))
    )
    (net (code "239") (name "Net-(D11-K)") (class "Default")
      (node (ref "D11") (pin "3") (pinfunction "K_3") (pintype "passive"))
      (node (ref "T5") (pin "3") (pinfunction "D_3") (pintype "passive"))
    )
    (net (code "240") (name "Net-(D13-K)") (class "Default")
      (node (ref "D13") (pin "3") (pinfunction "K_3") (pintype "passive"))
      (node (ref "T2") (pin "3") (pinfunction "D_3") (pintype "passive"))
    )
    (net (code "241") (name "Net-(IC13-OE)") (class "Default")
      (node (ref "IC13") (pin "10") (pinfunction "OE_10") (pintype "input"))
      (node (ref "R42") (pin "1") (pinfunction "1_1") (pintype "passive"))
    )
    (net (code "242") (name "Net-(IC22-OUT)") (class "Default")
      (node (ref "IC22") (pin "3") (pinfunction "OUT_3") (pintype "output"))
      (node (ref "R118") (pin "1") (pinfunction "1_1") (pintype "passive"))
    )
    (net (code "243") (name "unconnected-(IC13-A5-Pad6)") (class "Default")
      (node (ref "IC13") (pin "6") (pinfunction "A5_6") (pintype "bidirectional"))
    )
    (net (code "244") (name "unconnected-(IC13-A6-Pad7)") (class "Default")
      (node (ref "IC13") (pin "7") (pinfunction "A6_7") (pintype "bidirectional"))
    )
    (net (code "245") (name "unconnected-(IC13-A7-Pad8)") (class "Default")
      (node (ref "IC13") (pin "8") (pinfunction "A7_8") (pintype "bidirectional"))
    )
    (net (code "246") (name "unconnected-(IC13-A8-Pad9)") (class "Default")
      (node (ref "IC13") (pin "9") (pinfunction "A8_9") (pintype "bidirectional"))
    )
    (net (code "247") (name "unconnected-(IC13-B5-Pad15)") (class "Default")
      (node (ref "IC13") (pin "15") (pinfunction "B5_15") (pintype "bidirectional"))
    )
    (net (code "248") (name "unconnected-(IC13-B6-Pad14)") (class "Default")
      (node (ref "IC13") (pin "14") (pinfunction "B6_14") (pintype "bidirectional"))
    )
    (net (code "249") (name "unconnected-(IC13-B7-Pad13)") (class "Default")
      (node (ref "IC13") (pin "13") (pinfunction "B7_13") (pintype "bidirectional"))
    )
    (net (code "250") (name "unconnected-(IC13-B8-Pad12)") (class "Default")
      (node (ref "IC13") (pin "12") (pinfunction "B8_12") (pintype "bidirectional"))
    )
    (net (code "251") (name "unconnected-(JB1-C22_B35_T2_L16N-Pad32)") (class "Default")
      (node (ref "JB1") (pin "32") (pinfunction "C22_B35_T2_L16N_32") (pintype "bidirectional"))
    )
    (net (code "252") (name "unconnected-(JB1-D22_B35_T2_L16P-Pad34)") (class "Default")
      (node (ref "JB1") (pin "34") (pinfunction "D22_B35_T2_L16P_34") (pintype "bidirectional"))
    )
    (net (code "253") (name "unconnected-(JB1-MIO43-Pad22)") (class "Default")
      (node (ref "JB1") (pin "22") (pinfunction "MIO43_22") (pintype "bidirectional"))
    )
    (net (code "254") (name "unconnected-(JB1-MIO44-Pad20)") (class "Default")
      (node (ref "JB1") (pin "20") (pinfunction "MIO44_20") (pintype "bidirectional"))
    )
    (net (code "255") (name "unconnected-(JB1-NOSEQ-Pad8)") (class "Default")
      (node (ref "JB1") (pin "8") (pinfunction "NOSEQ_8") (pintype "passive"))
    )
    (net (code "256") (name "unconnected-(JB1-PGOOD-Pad29)") (class "Default")
      (node (ref "JB1") (pin "29") (pinfunction "PGOOD_29") (pintype "passive"))
    )
    (net (code "257") (name "unconnected-(JB1-PHY_COM-Pad13)") (class "Default")
      (node (ref "JB1") (pin "13") (pinfunction "PHY_COM_13") (pintype "passive+no_connect"))
    )
    (net (code "258") (name "unconnected-(JB1-VBAT_IN-Pad80)") (class "Default")
      (node (ref "JB1") (pin "80") (pinfunction "VBAT_IN_80") (pintype "power_in"))
    )
    (net (code "259") (name "unconnected-(JB2-1.5V-Pad20)") (class "Default")
      (node (ref "JB2") (pin "20") (pinfunction "1.5V_20") (pintype "power_in+no_connect"))
    )
    (net (code "260") (name "unconnected-(JB2-AA17_B33_T2_L17P-Pad32)") (class "Default")
      (node (ref "JB2") (pin "32") (pinfunction "AA17_B33_T2_L17P_32") (pintype "bidirectional"))
    )
    (net (code "261") (name "unconnected-(JB2-AA18_B33_T1_MRCC_L12N-Pad28)") (class "Default")
      (node (ref "JB2") (pin "28") (pinfunction "AA18_B33_T1_MRCC_L12N_28") (pintype "bidirectional"))
    )
    (net (code "262") (name "unconnected-(JB2-AA21_B33_T1_L8P-Pad16)") (class "Default")
      (node (ref "JB2") (pin "16") (pinfunction "AA21_B33_T1_L8P_16") (pintype "bidirectional"))
    )
    (net (code "263") (name "unconnected-(JB2-AA22_B33_T1_L7P-Pad12)") (class "Default")
      (node (ref "JB2") (pin "12") (pinfunction "AA22_B33_T1_L7P_12") (pintype "bidirectional"))
    )
    (net (code "264") (name "unconnected-(JB2-AB17_B33_T2_L17N-Pad34)") (class "Default")
      (node (ref "JB2") (pin "34") (pinfunction "AB17_B33_T2_L17N_34") (pintype "bidirectional"))
    )
    (net (code "265") (name "unconnected-(JB2-AB21_B33_T1_L8N-Pad18)") (class "Default")
      (node (ref "JB2") (pin "18") (pinfunction "AB21_B33_T1_L8N_18") (pintype "bidirectional"))
    )
    (net (code "266") (name "unconnected-(JB2-AB22_B33_T1_L7N-Pad14)") (class "Default")
      (node (ref "JB2") (pin "14") (pinfunction "AB22_B33_T1_L7N_14") (pintype "bidirectional"))
    )
    (net (code "267") (name "unconnected-(JB2-B13_IO0-Pad99)") (class "Default")
      (node (ref "JB2") (pin "99") (pinfunction "B13_IO0_99") (pintype "bidirectional"))
    )
    (net (code "268") (name "unconnected-(JB2-B13_IO25-Pad90)") (class "Default")
      (node (ref "JB2") (pin "90") (pinfunction "B13_IO25_90") (pintype "bidirectional"))
    )
    (net (code "269") (name "unconnected-(JB2-B33_VREF-Pad30)") (class "Default")
      (node (ref "JB2") (pin "30") (pinfunction "B33_VREF_30") (pintype "power_in+no_connect"))
    )
    (net (code "270") (name "unconnected-(JB2-R6_B13_T3_L19P-Pad91)") (class "Default")
      (node (ref "JB2") (pin "91") (pinfunction "R6_B13_T3_L19P_91") (pintype "bidirectional"))
    )
    (net (code "271") (name "unconnected-(JB2-RESIN-Pad17)") (class "Default")
      (node (ref "JB2") (pin "17") (pinfunction "RESIN_17") (pintype "passive"))
    )
    (net (code "272") (name "unconnected-(JB2-T4_B13_T3_L20P-Pad62)") (class "Default")
      (node (ref "JB2") (pin "62") (pinfunction "T4_B13_T3_L20P_62") (pintype "bidirectional"))
    )
    (net (code "273") (name "unconnected-(JB2-T6_B13_T3_VREF_L19N-Pad93)") (class "Default")
      (node (ref "JB2") (pin "93") (pinfunction "T6_B13_T3_VREF_L19N_93") (pintype "bidirectional"))
    )
    (net (code "274") (name "unconnected-(JB2-U4_B13_T3_L20N-Pad64)") (class "Default")
      (node (ref "JB2") (pin "64") (pinfunction "U4_B13_T3_L20N_64") (pintype "bidirectional"))
    )
    (net (code "275") (name "unconnected-(JB2-W16_B33_T2_SRCC_L14P-Pad25)") (class "Default")
      (node (ref "JB2") (pin "25") (pinfunction "W16_B33_T2_SRCC_L14P_25") (pintype "bidirectional"))
    )
    (net (code "276") (name "unconnected-(JB2-W17_B33_T2_MRCC_L13P-Pad21)") (class "Default")
      (node (ref "JB2") (pin "21") (pinfunction "W17_B33_T2_MRCC_L13P_21") (pintype "bidirectional"))
    )
    (net (code "277") (name "unconnected-(JB2-W18_B33_T2_MRCC_L13N-Pad23)") (class "Default")
      (node (ref "JB2") (pin "23") (pinfunction "W18_B33_T2_MRCC_L13N_23") (pintype "bidirectional"))
    )
    (net (code "278") (name "unconnected-(JB2-W20_B33_T0_L4P-Pad13)") (class "Default")
      (node (ref "JB2") (pin "13") (pinfunction "W20_B33_T0_L4P_13") (pintype "passive"))
    )
    (net (code "279") (name "unconnected-(JB2-W21_B33_T0_L4N-Pad15)") (class "Default")
      (node (ref "JB2") (pin "15") (pinfunction "W21_B33_T0_L4N_15") (pintype "passive"))
    )
    (net (code "280") (name "unconnected-(JB2-Y8_B13_T1_MRCC_L12N-Pad47)") (class "Default")
      (node (ref "JB2") (pin "47") (pinfunction "Y8_B13_T1_MRCC_L12N_47") (pintype "bidirectional"))
    )
    (net (code "281") (name "unconnected-(JB2-Y16_B33_T2_SRCC_L14N-Pad27)") (class "Default")
      (node (ref "JB2") (pin "27") (pinfunction "Y16_B33_T2_SRCC_L14N_27") (pintype "bidirectional"))
    )
    (net (code "282") (name "unconnected-(JB2-Y18_B33_T1_MRCC_L12P-Pad26)") (class "Default")
      (node (ref "JB2") (pin "26") (pinfunction "Y18_B33_T1_MRCC_L12P_26") (pintype "bidirectional"))
    )
    (net (code "283") (name "unconnected-(JB3-L18_B34_T1_MRCC_L12P-Pad32)") (class "Default")
      (node (ref "JB3") (pin "32") (pinfunction "L18_B34_T1_MRCC_L12P_32") (pintype "bidirectional"))
    )
    (net (code "284") (name "unconnected-(JB3-L19_B34_T1_MRCC_L12N-Pad34)") (class "Default")
      (node (ref "JB3") (pin "34") (pinfunction "L19_B34_T1_MRCC_L12N_34") (pintype "bidirectional"))
    )
    (net (code "285") (name "unconnected-(JB3-L21_B34_T1_L10P-Pad25)") (class "Default")
      (node (ref "JB3") (pin "25") (pinfunction "L21_B34_T1_L10P_25") (pintype "bidirectional"))
    )
    (net (code "286") (name "unconnected-(JB3-L22_B34_T1_L10N-Pad27)") (class "Default")
      (node (ref "JB3") (pin "27") (pinfunction "L22_B34_T1_L10N_27") (pintype "bidirectional"))
    )
    (net (code "287") (name "unconnected-(JB3-N17_B34_T0_L5P-Pad26)") (class "Default")
      (node (ref "JB3") (pin "26") (pinfunction "N17_B34_T0_L5P_26") (pintype "bidirectional"))
    )
    (net (code "288") (name "unconnected-(JB3-N18_B34_T0_L5N-Pad28)") (class "Default")
      (node (ref "JB3") (pin "28") (pinfunction "N18_B34_T0_L5N_28") (pintype "bidirectional"))
    )
    (net (code "289") (name "unconnected-(JB3-N19_B34_SRCC_L14P-Pad57)") (class "Default")
      (node (ref "JB3") (pin "57") (pinfunction "N19_B34_SRCC_L14P_57") (pintype "bidirectional"))
    )
    (net (code "290") (name "unconnected-(JB3-N20_B34_SRCC_L14N-Pad59)") (class "Default")
      (node (ref "JB3") (pin "59") (pinfunction "N20_B34_SRCC_L14N_59") (pintype "bidirectional"))
    )
    (net (code "291") (name "unconnected-(JB3-OTG-DP-Pad48)") (class "Default")
      (node (ref "JB3") (pin "48") (pinfunction "OTG-DP_48") (pintype "power_in"))
    )
    (net (code "292") (name "unconnected-(JB3-SIN_N-Pad1)") (class "Default")
      (node (ref "JB3") (pin "1") (pinfunction "SIN_N_1") (pintype "power_in"))
    )
    (net (code "293") (name "unconnected-(JB3-SIN_P-Pad3)") (class "Default")
      (node (ref "JB3") (pin "3") (pinfunction "SIN_P_3") (pintype "power_in"))
    )
    (net (code "294") (name "unconnected-(JB3-SOUT_N-Pad2)") (class "Default")
      (node (ref "JB3") (pin "2") (pinfunction "SOUT_N_2") (pintype "passive"))
    )
    (net (code "295") (name "unconnected-(JB3-SOUT_P-Pad4)") (class "Default")
      (node (ref "JB3") (pin "4") (pinfunction "SOUT_P_4") (pintype "passive"))
    )
  )
)
